# schematic_smart_home.net
KiCad netlist of a schematic drawn in Altium Designer
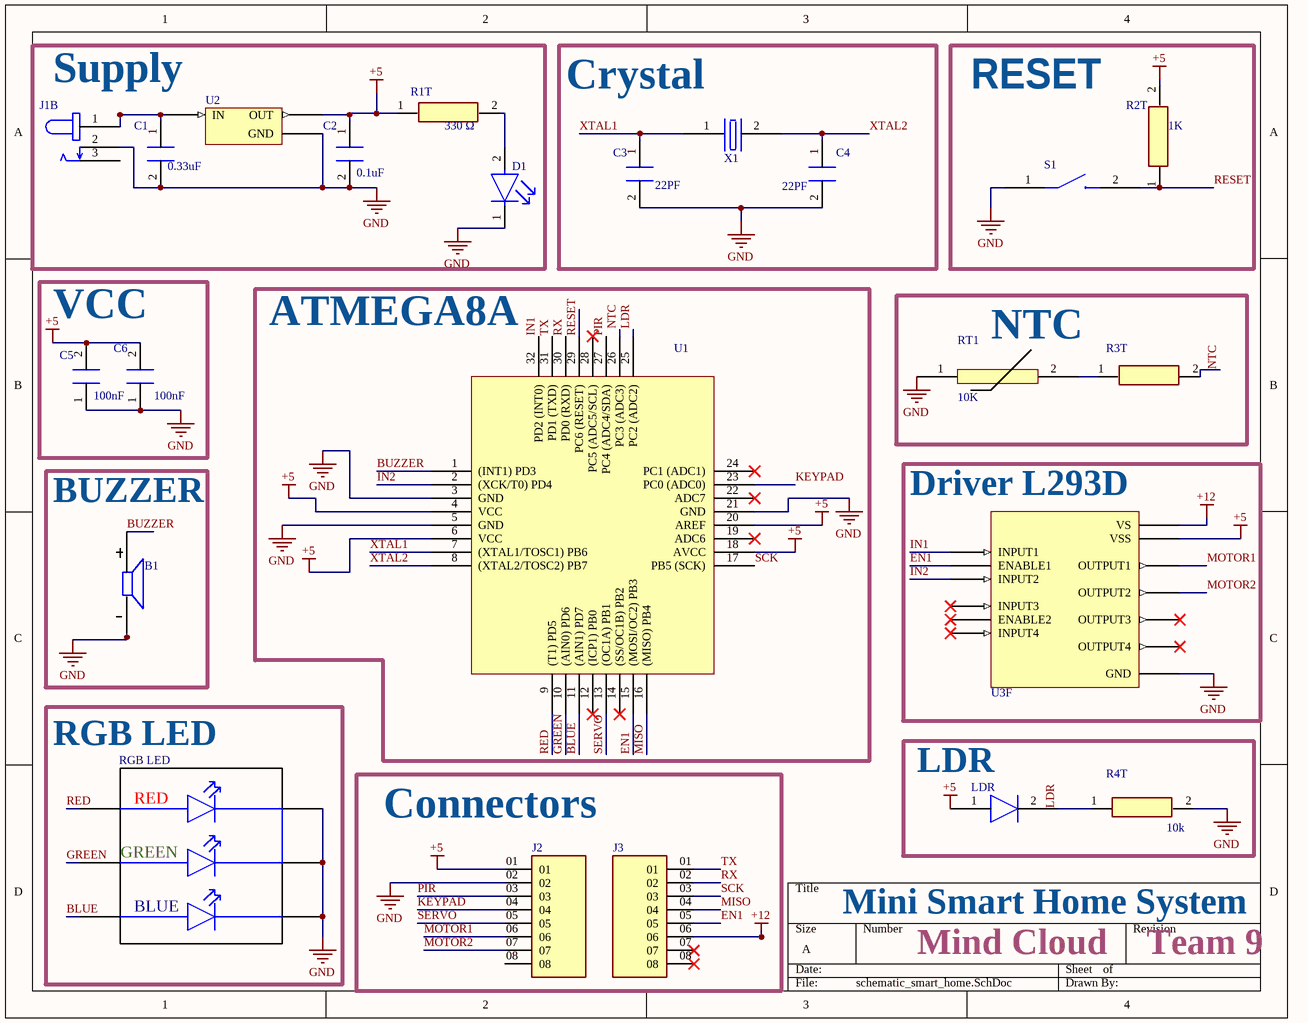
[diagram p0: schematic_smart_home.SchDoc]

(export (version "E")
  (design (tool "Eeschema 10.0.6"))
  (components
    (comp (ref "B1")
      (value "CMT-1271-88-SMT-TR")
      (footprint "PcbLib_buzzer:PCBComponent_1")
      (description "88dB Passive (external drive) Electromagnetic Type 2.4kHz Buzzers ROHS")
      (libsource (lib "Schlib_buzzer") (part "buzzer"))
    )
    (comp (ref "C1")
      (value "0.33uF")
      (footprint "PcbLib_capacitor_1206:PCBComponent_1")
      (description "100V 100nF C0G ±5% 1206 Multilayer Ceramic Capacitors MLCC - SMD/SMT ROHS")
      (fields (field (name "MANUFACTOR PART NUMBER") "GRM31C5C2A104JA01L"))
      (libsource (lib "Schlib_capacitor_1206") (part "capacitor_1206 CODE"))
    )
    (comp (ref "C2")
      (value "0.1uF")
      (footprint "PcbLib_capacitor_1206:PCBComponent_1")
      (description "100V 100nF C0G ±5% 1206 Multilayer Ceramic Capacitors MLCC - SMD/SMT ROHS")
      (fields (field (name "MANUFACTOR PART NUMBER") "GRM31C5C2A104JA01L"))
      (libsource (lib "Schlib_capacitor_1206") (part "capacitor_1206 CODE"))
    )
    (comp (ref "C3")
      (value "22PF")
      (footprint "PcbLib_capacitor_1206:PCBComponent_1")
      (description "100V 100nF C0G ±5% 1206 Multilayer Ceramic Capacitors MLCC - SMD/SMT ROHS")
      (fields (field (name "MANUFACTOR PART NUMBER") "GRM31C5C2A104JA01L"))
      (libsource (lib "Schlib_capacitor_1206") (part "capacitor_1206 CODE"))
    )
    (comp (ref "C4")
      (value "22PF")
      (footprint "PcbLib_capacitor_1206:PCBComponent_1")
      (description "100V 100nF C0G ±5% 1206 Multilayer Ceramic Capacitors MLCC - SMD/SMT ROHS")
      (fields (field (name "MANUFACTOR PART NUMBER") "GRM31C5C2A104JA01L"))
      (libsource (lib "Schlib_capacitor_1206") (part "capacitor_1206 CODE"))
    )
    (comp (ref "C5")
      (value "100nF")
      (footprint "PcbLib_capacitor_1206:PCBComponent_1")
      (description "100V 100nF C0G ±5% 1206 Multilayer Ceramic Capacitors MLCC - SMD/SMT ROHS")
      (fields (field (name "MANUFACTOR PART NUMBER") "GRM31C5C2A104JA01L"))
      (libsource (lib "Schlib_capacitor_1206") (part "capacitor_1206 CODE"))
    )
    (comp (ref "C6")
      (value "100nF")
      (footprint "PcbLib_capacitor_1206:PCBComponent_1")
      (description "100V 100nF C0G ±5% 1206 Multilayer Ceramic Capacitors MLCC - SMD/SMT ROHS")
      (fields (field (name "MANUFACTOR PART NUMBER") "GRM31C5C2A104JA01L"))
      (libsource (lib "Schlib_capacitor_1206") (part "capacitor_1206 CODE"))
    )
    (comp (ref "D1")
      (value "LTST-C191TBKT")
      (footprint "FP-LTST-C191TBKT-MFG")
      (description "LED BLUE CLEAR CHIP SMD")
      (libsource (lib "Altium Content Vault") (part "8706943c75ba83719d021d2fdc84c58"))
    )
    (comp (ref "J1")
      (value "PJ-002AH-SMT-TR")
      (footprint "PcbLib_Dc connector:PCBComponent_1")
      (description "SMD DC Power Connectors ROHS")
      (fields (field (name "MANUFACTURER") "CUI"))
      (libsource (lib "Schlib_DC connector") (part "DC connector"))
    )
    (comp (ref "J2")
      (value "TSM-108-01-L-SV")
      (footprint "Header")
      (fields (field (name "MF") "Samtec"))
      (libsource (lib "TSM-108-01-L-SV") (part "TSM-108-01-L-SV"))
    )
    (comp (ref "J3")
      (value "TSM-108-01-L-SV")
      (footprint "Header")
      (fields (field (name "MF") "Samtec"))
      (libsource (lib "") (part "TSM-108-01-L-SV_1"))
    )
    (comp (ref "LDR")
      (value "RS1G")
      (footprint "PcbLib_LDR sensor:PCBComponent_1")
      (description "1A Independent Type 1.3V@1A 400V SMA(DO-214AC) Diodes - General Purpose ROHS")
      (libsource (lib "Schlib_LDR sensor") (part "LDR sensor"))
    )
    (comp (ref "R1")
      (value "330 Ω")
      (footprint "PcbLib_resistor:RESC1005X04N")
      (description "500mW Thick Film Resistors 400V ±100ppm/℃ ±1% 100Ω 1210 Chip Resistor - Surface Mount ROHS")
      (fields
        (field (name "MANUFACTURER") "PANASONIC")
        (field (name "MANUFACTURER PART NUMBER") "ERJ-U14F1000U")
      )
      (libsource (lib "Schlib_resistor") (part "Resistor"))
    )
    (comp (ref "R2")
      (value "1K")
      (footprint "PcbLib_resistor:RESC1005X04N")
      (description "500mW Thick Film Resistors 400V ±100ppm/℃ ±1% 100Ω 1210 Chip Resistor - Surface Mount ROHS")
      (fields
        (field (name "MANUFACTURER") "PANASONIC")
        (field (name "MANUFACTURER PART NUMBER") "ERJ-U14F1000U")
      )
      (libsource (lib "") (part "Resistor_1"))
    )
    (comp (ref "R3")
      (value "resistor SMD")
      (footprint "RESC1005X04N")
      (description "500mW Thick Film Resistors 400V ±100ppm/℃ ±1% 100Ω 1210 Chip Resistor - Surface Mount ROHS")
      (fields
        (field (name "MANUFACTURER") "PANASONIC")
        (field (name "MANUFACTURER PART NUMBER") "ERJ-U14F1000U")
      )
      (libsource (lib "Schlib_resistor") (part "Resistor"))
    )
    (comp (ref "R4")
      (value "10k")
      (footprint "RESC1005X04N")
      (description "500mW Thick Film Resistors 400V ±100ppm/℃ ±1% 100Ω 1210 Chip Resistor - Surface Mount ROHS")
      (fields
        (field (name "MANUFACTURER") "PANASONIC")
        (field (name "MANUFACTURER PART NUMBER") "ERJ-U14F1000U")
      )
      (libsource (lib "Schlib_resistor") (part "Resistor"))
    )
    (comp (ref "RGB LED")
      (value "ASMB-TTF2-0B20B")
      (footprint "PcbLib_RGB LED:PCBComponent_1")
      (description "PLCC-6 RGB LEDs ROHS")
      (libsource (lib "Schlib_RGB LED") (part "RGB LED"))
    )
    (comp (ref "RT1")
      (value "10K")
      (footprint "RESC1005X04N")
      (description "10kΩ ±0.5% 3380K ±0.7% 0402 NTC Thermistors ROHS\r\nRecommended For You")
      (fields
        (field (name "MANUFACTURER") "Murata Electronics")
        (field (name "MANUFACTURER PART NUMBER") "NCU15XH103D6SRC")
      )
      (libsource (lib "schli_temperture_sensor_NTC") (part "NTC temperature sensor"))
    )
    (comp (ref "S1")
      (value "TS16-1212-85-BK-100-SMT-TR")
      (footprint "PcbLib_switch:PCBComponent_1")
      (description "50mA Standing paste SPST - normally open 100gf 12V Tactile Switches ROHS")
      (libsource (lib "Schlib_switch") (part "switch"))
    )
    (comp (ref "U1")
      (value "ATMEGA8A-AU_C16190")
      (footprint "TQFP80P900X900X120-32N")
      (description "8KB 1KB FLASH 23 2.7V~5.5V AVR 16MHz TQFP-32(7x7) Microcontrollers (MCU/MPU/SOC) ROHS")
      (fields
        (field (name "MANUFACTURER") "Microchip Tech")
        (field (name "MANUFACTURER PART NUMBER") "ATMEGA8A-AU")
      )
      (libsource (lib "Schematic_library_ATMEGA8A") (part "ATMEGA8A-AU"))
    )
    (comp (ref "U2")
      (value "MC78M05ACDTRKG")
      (footprint "PcbLib_regulator 5v:PCBComponent_1")
      (fields (field (name "MANUFACTURER") "onsemi"))
      (libsource (lib "Schlib_regulator 5v") (part "regulator"))
    )
    (comp (ref "U3")
      (value "Driver L293D")
      (footprint "SOIC127P1030X265-20N")
      (description "SOIC-20-300mil Stepper Motor Driver ROHS")
      (fields
        (field (name "MANUFACTURER") "STMicroelectronics")
        (field (name "MANUFACTURER PART NUMBER") "L293DD013TR")
      )
      (libsource (lib "Schlib_Driver L293D") (part "Driver L293D"))
    )
    (comp (ref "X1")
      (value "16 MHZ")
      (footprint "PcbLib_crystal:PCBComponent_1")
      (description "16MHz ±30ppm ±50ppm HC-49S-SMD Crystals ROHS")
      (libsource (lib "Schlib_crystal") (part "crystal"))
    )
  )
  (nets
    (net (code "1") (name "+5") (class "Default")
      (node (ref "C2") (pin "1") (pinfunction "1_1") (pintype "passive"))
      (node (ref "C5") (pin "2") (pinfunction "2_2") (pintype "passive"))
      (node (ref "C6") (pin "2") (pinfunction "2_2") (pintype "passive"))
      (node (ref "J2") (pin "01") (pinfunction "01_01") (pintype "passive"))
      (node (ref "LDR") (pin "1") (pinfunction "1_1") (pintype "passive"))
      (node (ref "R1") (pin "1") (pinfunction "1_1") (pintype "passive"))
      (node (ref "R2") (pin "2") (pinfunction "2_2") (pintype "passive"))
      (node (ref "U1") (pin "18") (pinfunction "AVCC_18") (pintype "passive"))
      (node (ref "U1") (pin "20") (pinfunction "AREF_20") (pintype "passive"))
      (node (ref "U1") (pin "4") (pinfunction "VCC_4") (pintype "passive"))
      (node (ref "U1") (pin "6") (pinfunction "VCC_6") (pintype "passive"))
      (node (ref "U2") (pin "2") (pinfunction "OUT_2") (pintype "output"))
      (node (ref "U3") (pin "7") (pinfunction "VSS_7") (pintype "passive"))
    )
    (net (code "2") (name "+12") (class "Default")
      (node (ref "J3") (pin "06") (pinfunction "06_06") (pintype "passive"))
      (node (ref "U3") (pin "6") (pinfunction "VS_6") (pintype "passive"))
    )
    (net (code "3") (name "/BLUE") (class "Default")
      (node (ref "RGB LED") (pin "5") (pinfunction "5_5") (pintype "passive"))
      (node (ref "U1") (pin "11") (pinfunction "(AIN1)_PD7_11") (pintype "passive"))
    )
    (net (code "4") (name "/BUZZER") (class "Default")
      (node (ref "B1") (pin "1") (pinfunction "1_1") (pintype "passive"))
      (node (ref "U1") (pin "1") (pinfunction "(INT1)_PD3_1") (pintype "passive"))
    )
    (net (code "5") (name "/EN1") (class "Default")
      (node (ref "J3") (pin "05") (pinfunction "05_05") (pintype "passive"))
      (node (ref "U1") (pin "15") (pinfunction "(MOSI/OC2)_PB3_15") (pintype "passive"))
      (node (ref "U3") (pin "2") (pinfunction "ENABLE1_2") (pintype "passive"))
    )
    (net (code "6") (name "/GREEN") (class "Default")
      (node (ref "RGB LED") (pin "3") (pinfunction "3_3") (pintype "passive"))
      (node (ref "U1") (pin "10") (pinfunction "(AIN0)_PD6_10") (pintype "passive"))
    )
    (net (code "7") (name "/IN1") (class "Default")
      (node (ref "U1") (pin "32") (pinfunction "PD2_(INT0)_32") (pintype "passive"))
      (node (ref "U3") (pin "1") (pinfunction "INPUT1_1") (pintype "input"))
    )
    (net (code "8") (name "/IN2") (class "Default")
      (node (ref "U1") (pin "2") (pinfunction "(XCK/T0)_PD4_2") (pintype "passive"))
      (node (ref "U3") (pin "3") (pinfunction "INPUT2_3") (pintype "input"))
    )
    (net (code "9") (name "/KEYPAD") (class "Default")
      (node (ref "J2") (pin "04") (pinfunction "04_04") (pintype "passive"))
      (node (ref "U1") (pin "23") (pinfunction "PC0_(ADC0)_23") (pintype "passive"))
    )
    (net (code "10") (name "/LDR") (class "Default")
      (node (ref "LDR") (pin "2") (pinfunction "2_2") (pintype "passive"))
      (node (ref "R4") (pin "1") (pinfunction "1_1") (pintype "passive"))
      (node (ref "U1") (pin "25") (pinfunction "PC2_(ADC2)_25") (pintype "passive"))
    )
    (net (code "11") (name "/MISO") (class "Default")
      (node (ref "J3") (pin "04") (pinfunction "04_04") (pintype "passive"))
      (node (ref "U1") (pin "16") (pinfunction "(MISO)_PB4_16") (pintype "passive"))
    )
    (net (code "12") (name "/MOTOR1") (class "Default")
      (node (ref "J2") (pin "06") (pinfunction "06_06") (pintype "passive"))
      (node (ref "U3") (pin "9") (pinfunction "OUTPUT1_9") (pintype "output"))
    )
    (net (code "13") (name "/MOTOR2") (class "Default")
      (node (ref "J2") (pin "07") (pinfunction "07_07") (pintype "passive"))
      (node (ref "U3") (pin "10") (pinfunction "OUTPUT2_10") (pintype "output"))
    )
    (net (code "14") (name "/NTC") (class "Default")
      (node (ref "R3") (pin "2") (pinfunction "2_2") (pintype "passive"))
      (node (ref "U1") (pin "26") (pinfunction "PC3_(ADC3)_26") (pintype "passive"))
    )
    (net (code "15") (name "/PIR") (class "Default")
      (node (ref "J2") (pin "03") (pinfunction "03_03") (pintype "passive"))
      (node (ref "U1") (pin "27") (pinfunction "PC4_(ADC4/SDA)_27") (pintype "passive"))
    )
    (net (code "16") (name "/RED") (class "Default")
      (node (ref "RGB LED") (pin "1") (pinfunction "1_1") (pintype "passive"))
      (node (ref "U1") (pin "9") (pinfunction "(T1)_PD5_9") (pintype "passive"))
    )
    (net (code "17") (name "/RESET") (class "Default")
      (node (ref "R2") (pin "1") (pinfunction "1_1") (pintype "passive"))
      (node (ref "S1") (pin "2") (pinfunction "2_2") (pintype "passive"))
      (node (ref "U1") (pin "29") (pinfunction "PC6_(RESET)_29") (pintype "passive"))
    )
    (net (code "18") (name "/RX") (class "Default")
      (node (ref "J3") (pin "02") (pinfunction "02_02") (pintype "passive"))
      (node (ref "U1") (pin "30") (pinfunction "PD0_(RXD)_30") (pintype "passive"))
    )
    (net (code "19") (name "/SCK") (class "Default")
      (node (ref "J3") (pin "03") (pinfunction "03_03") (pintype "passive"))
      (node (ref "U1") (pin "17") (pinfunction "PB5_(SCK)_17") (pintype "passive"))
    )
    (net (code "20") (name "/SERVO") (class "Default")
      (node (ref "J2") (pin "05") (pinfunction "05_05") (pintype "passive"))
      (node (ref "U1") (pin "13") (pinfunction "(OC1A)_PB1_13") (pintype "passive"))
    )
    (net (code "21") (name "/TX") (class "Default")
      (node (ref "J3") (pin "01") (pinfunction "01_01") (pintype "passive"))
      (node (ref "U1") (pin "31") (pinfunction "PD1_(TXD)_31") (pintype "passive"))
    )
    (net (code "22") (name "/XTAL1") (class "Default")
      (node (ref "C3") (pin "1") (pinfunction "1_1") (pintype "passive"))
      (node (ref "U1") (pin "7") (pinfunction "(XTAL1/TOSC1)_PB6_7") (pintype "passive"))
      (node (ref "X1") (pin "1") (pinfunction "1_1") (pintype "passive"))
    )
    (net (code "23") (name "/XTAL2") (class "Default")
      (node (ref "C4") (pin "1") (pinfunction "1_1") (pintype "passive"))
      (node (ref "U1") (pin "8") (pinfunction "(XTAL2/TOSC2)_PB7_8") (pintype "passive"))
      (node (ref "X1") (pin "2") (pinfunction "2_2") (pintype "passive"))
    )
    (net (code "24") (name "GND") (class "Default")
      (node (ref "B1") (pin "2") (pinfunction "2_2") (pintype "passive"))
      (node (ref "C1") (pin "2") (pinfunction "2_2") (pintype "passive"))
      (node (ref "C2") (pin "2") (pinfunction "2_2") (pintype "passive"))
      (node (ref "C3") (pin "2") (pinfunction "2_2") (pintype "passive"))
      (node (ref "C4") (pin "2") (pinfunction "2_2") (pintype "passive"))
      (node (ref "C5") (pin "1") (pinfunction "1_1") (pintype "passive"))
      (node (ref "C6") (pin "1") (pinfunction "1_1") (pintype "passive"))
      (node (ref "D1") (pin "1") (pinfunction "C_1") (pintype "passive"))
      (node (ref "J1") (pin "2") (pinfunction "2_2") (pintype "passive"))
      (node (ref "J2") (pin "02") (pinfunction "02_02") (pintype "passive"))
      (node (ref "R4") (pin "2") (pinfunction "2_2") (pintype "passive"))
      (node (ref "RGB LED") (pin "2") (pinfunction "2_2") (pintype "passive"))
      (node (ref "RGB LED") (pin "4") (pinfunction "4_4") (pintype "passive"))
      (node (ref "RGB LED") (pin "6") (pinfunction "6_6") (pintype "passive"))
      (node (ref "RT1") (pin "1") (pinfunction "1_1") (pintype "passive"))
      (node (ref "S1") (pin "1") (pinfunction "1_1") (pintype "passive"))
      (node (ref "U1") (pin "21") (pinfunction "GND_21") (pintype "passive"))
      (node (ref "U1") (pin "3") (pinfunction "GND_3") (pintype "passive"))
      (node (ref "U1") (pin "5") (pinfunction "GND_5") (pintype "passive"))
      (node (ref "U2") (pin "3") (pinfunction "GND_3") (pintype "passive"))
      (node (ref "U3") (pin "13") (pinfunction "GND_13") (pintype "passive"))
    )
    (net (code "25") (name "Net-(D1-A)") (class "Default")
      (node (ref "D1") (pin "2") (pinfunction "A_2") (pintype "passive"))
      (node (ref "R1") (pin "2") (pinfunction "2_2") (pintype "passive"))
    )
    (net (code "26") (name "Net-(R3-Pad1)") (class "Default")
      (node (ref "R3") (pin "1") (pinfunction "1_1") (pintype "passive"))
      (node (ref "RT1") (pin "2") (pinfunction "2_2") (pintype "passive"))
    )
    (net (code "27") (name "Net-(U2-IN)") (class "Default")
      (node (ref "C1") (pin "1") (pinfunction "1_1") (pintype "passive"))
      (node (ref "J1") (pin "1") (pinfunction "1_1") (pintype "passive"))
      (node (ref "U2") (pin "1") (pinfunction "IN_1") (pintype "input"))
    )
    (net (code "28") (name "unconnected-(J1-Pad3)") (class "Default")
      (node (ref "J1") (pin "3") (pinfunction "3_3") (pintype "passive"))
    )
    (net (code "29") (name "unconnected-(J2-Pad08)") (class "Default")
      (node (ref "J2") (pin "08") (pinfunction "08_08") (pintype "passive"))
    )
    (net (code "30") (name "unconnected-(J3-Pad07)") (class "Default")
      (node (ref "J3") (pin "07") (pinfunction "07_07") (pintype "passive+no_connect"))
    )
    (net (code "31") (name "unconnected-(J3-Pad08)") (class "Default")
      (node (ref "J3") (pin "08") (pinfunction "08_08") (pintype "passive+no_connect"))
    )
    (net (code "32") (name "unconnected-(U1-(ICP1)_PB0-Pad12)") (class "Default")
      (node (ref "U1") (pin "12") (pinfunction "(ICP1)_PB0_12") (pintype "passive+no_connect"))
    )
    (net (code "33") (name "unconnected-(U1-(SS{slash}OC1B)_PB2-Pad14)") (class "Default")
      (node (ref "U1") (pin "14") (pinfunction "(SS/OC1B)_PB2_14") (pintype "passive+no_connect"))
    )
    (net (code "34") (name "unconnected-(U1-ADC6-Pad19)") (class "Default")
      (node (ref "U1") (pin "19") (pinfunction "ADC6_19") (pintype "passive+no_connect"))
    )
    (net (code "35") (name "unconnected-(U1-ADC7-Pad22)") (class "Default")
      (node (ref "U1") (pin "22") (pinfunction "ADC7_22") (pintype "passive+no_connect"))
    )
    (net (code "36") (name "unconnected-(U1-PC1_(ADC1)-Pad24)") (class "Default")
      (node (ref "U1") (pin "24") (pinfunction "PC1_(ADC1)_24") (pintype "passive+no_connect"))
    )
    (net (code "37") (name "unconnected-(U1-PC5_(ADC5{slash}SCL)-Pad28)") (class "Default")
      (node (ref "U1") (pin "28") (pinfunction "PC5_(ADC5/SCL)_28") (pintype "passive+no_connect"))
    )
    (net (code "38") (name "unconnected-(U3F-ENABLE2-Pad5)") (class "Default")
      (node (ref "U3") (pin "5") (pinfunction "ENABLE2_5") (pintype "passive+no_connect"))
    )
    (net (code "39") (name "unconnected-(U3F-INPUT3-Pad4)") (class "Default")
      (node (ref "U3") (pin "4") (pinfunction "INPUT3_4") (pintype "input+no_connect"))
    )
    (net (code "40") (name "unconnected-(U3F-INPUT4-Pad6)") (class "Default")
      (node (ref "U3") (pin "6") (pinfunction "INPUT4_6") (pintype "input+no_connect"))
    )
    (net (code "41") (name "unconnected-(U3F-OUTPUT3-Pad11)") (class "Default")
      (node (ref "U3") (pin "11") (pinfunction "OUTPUT3_11") (pintype "output+no_connect"))
    )
    (net (code "42") (name "unconnected-(U3F-OUTPUT4-Pad12)") (class "Default")
      (node (ref "U3") (pin "12") (pinfunction "OUTPUT4_12") (pintype "output+no_connect"))
    )
  )
)
